# autoset-main.net
KiCad netlist of a schematic drawn in EAGLE
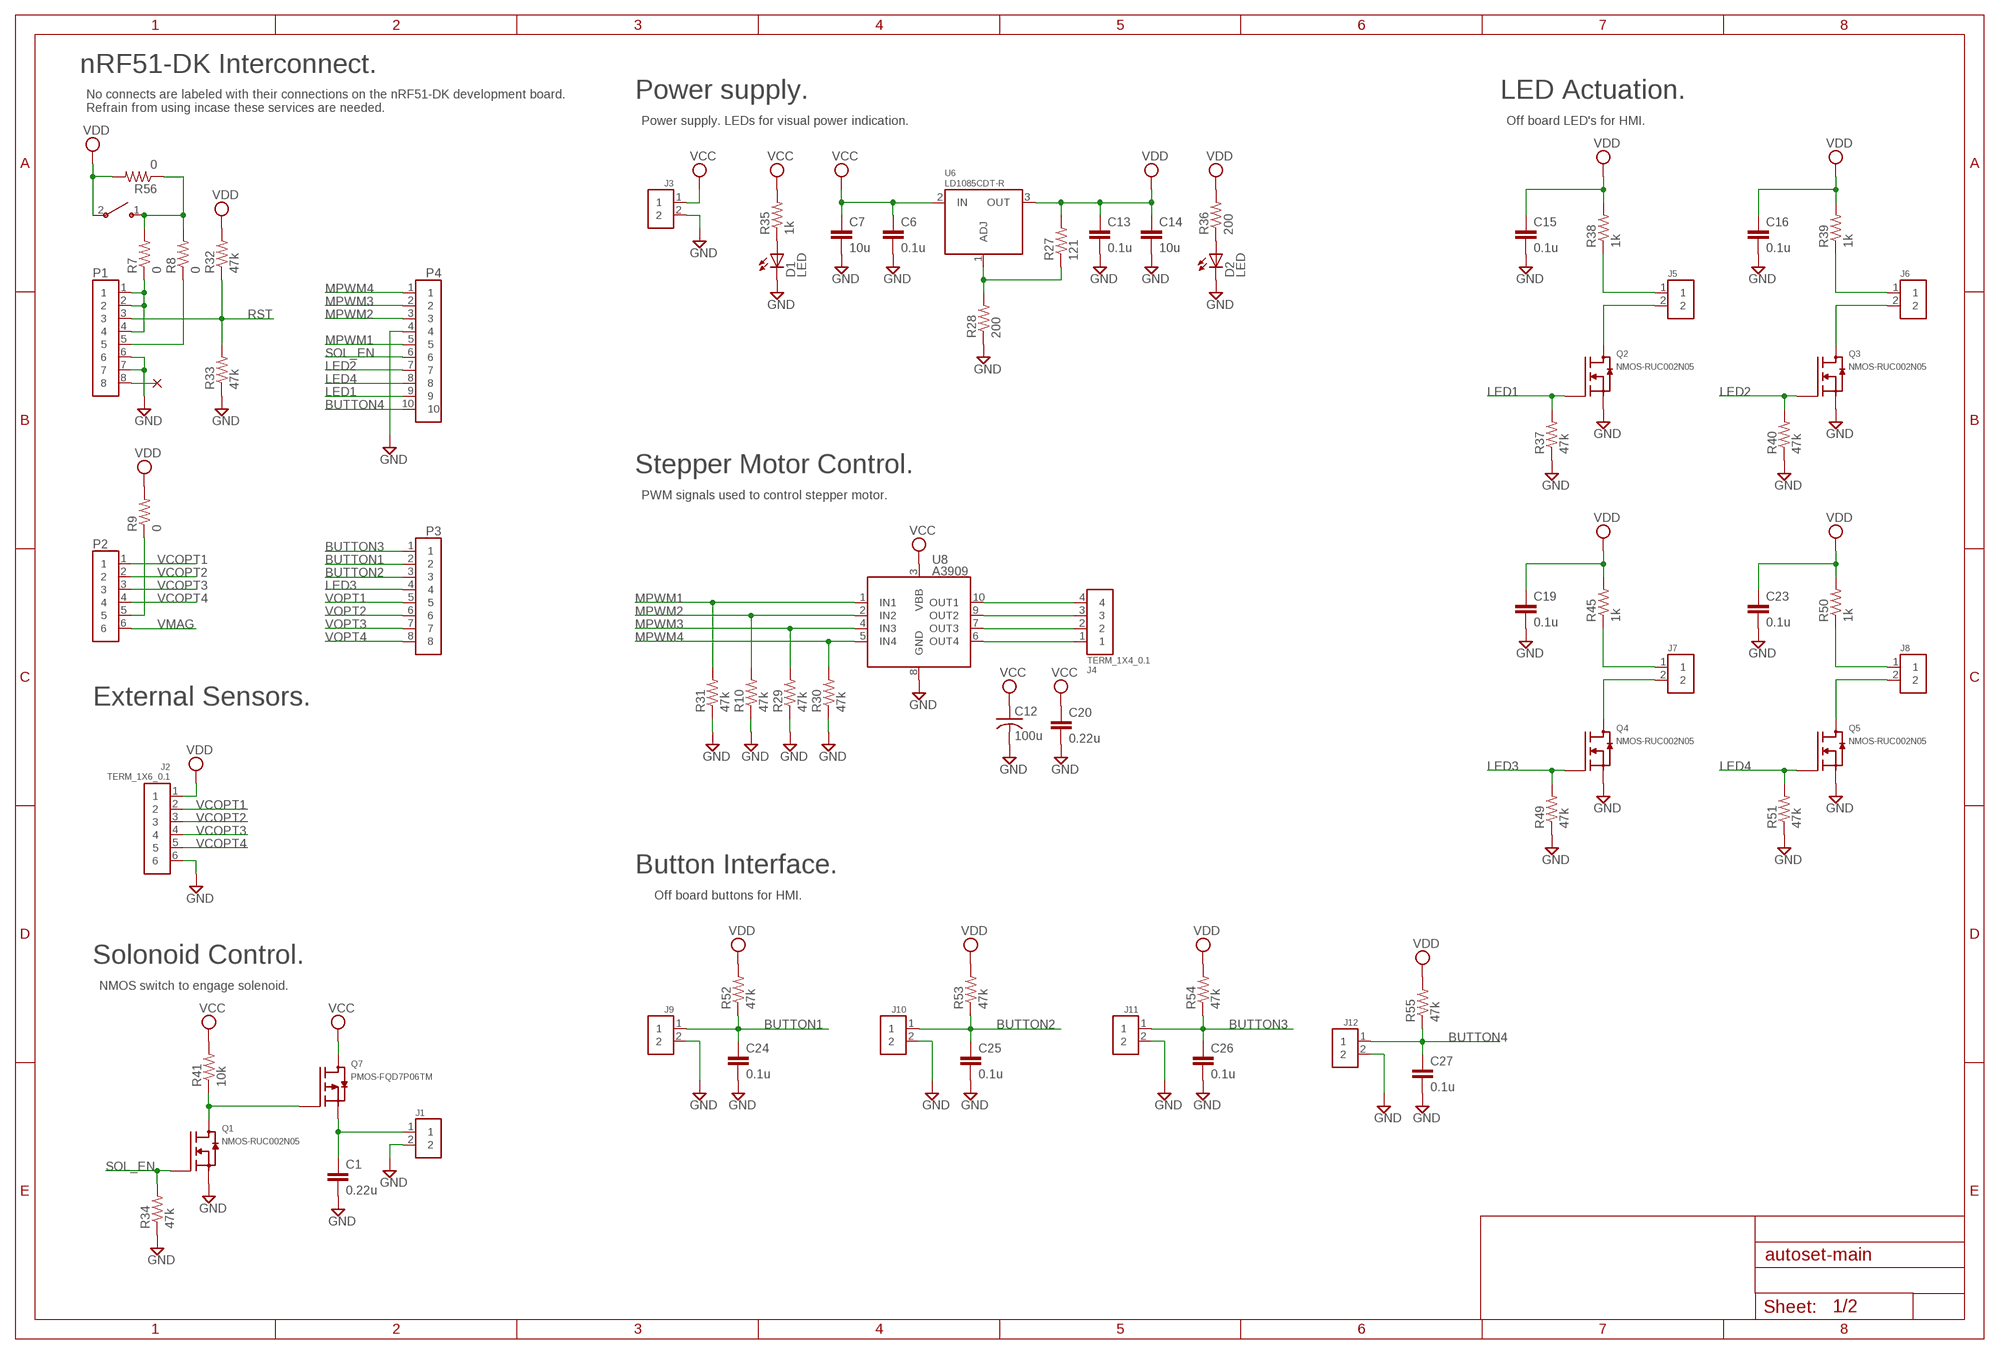
[diagram p0: schematic, sheet 1]
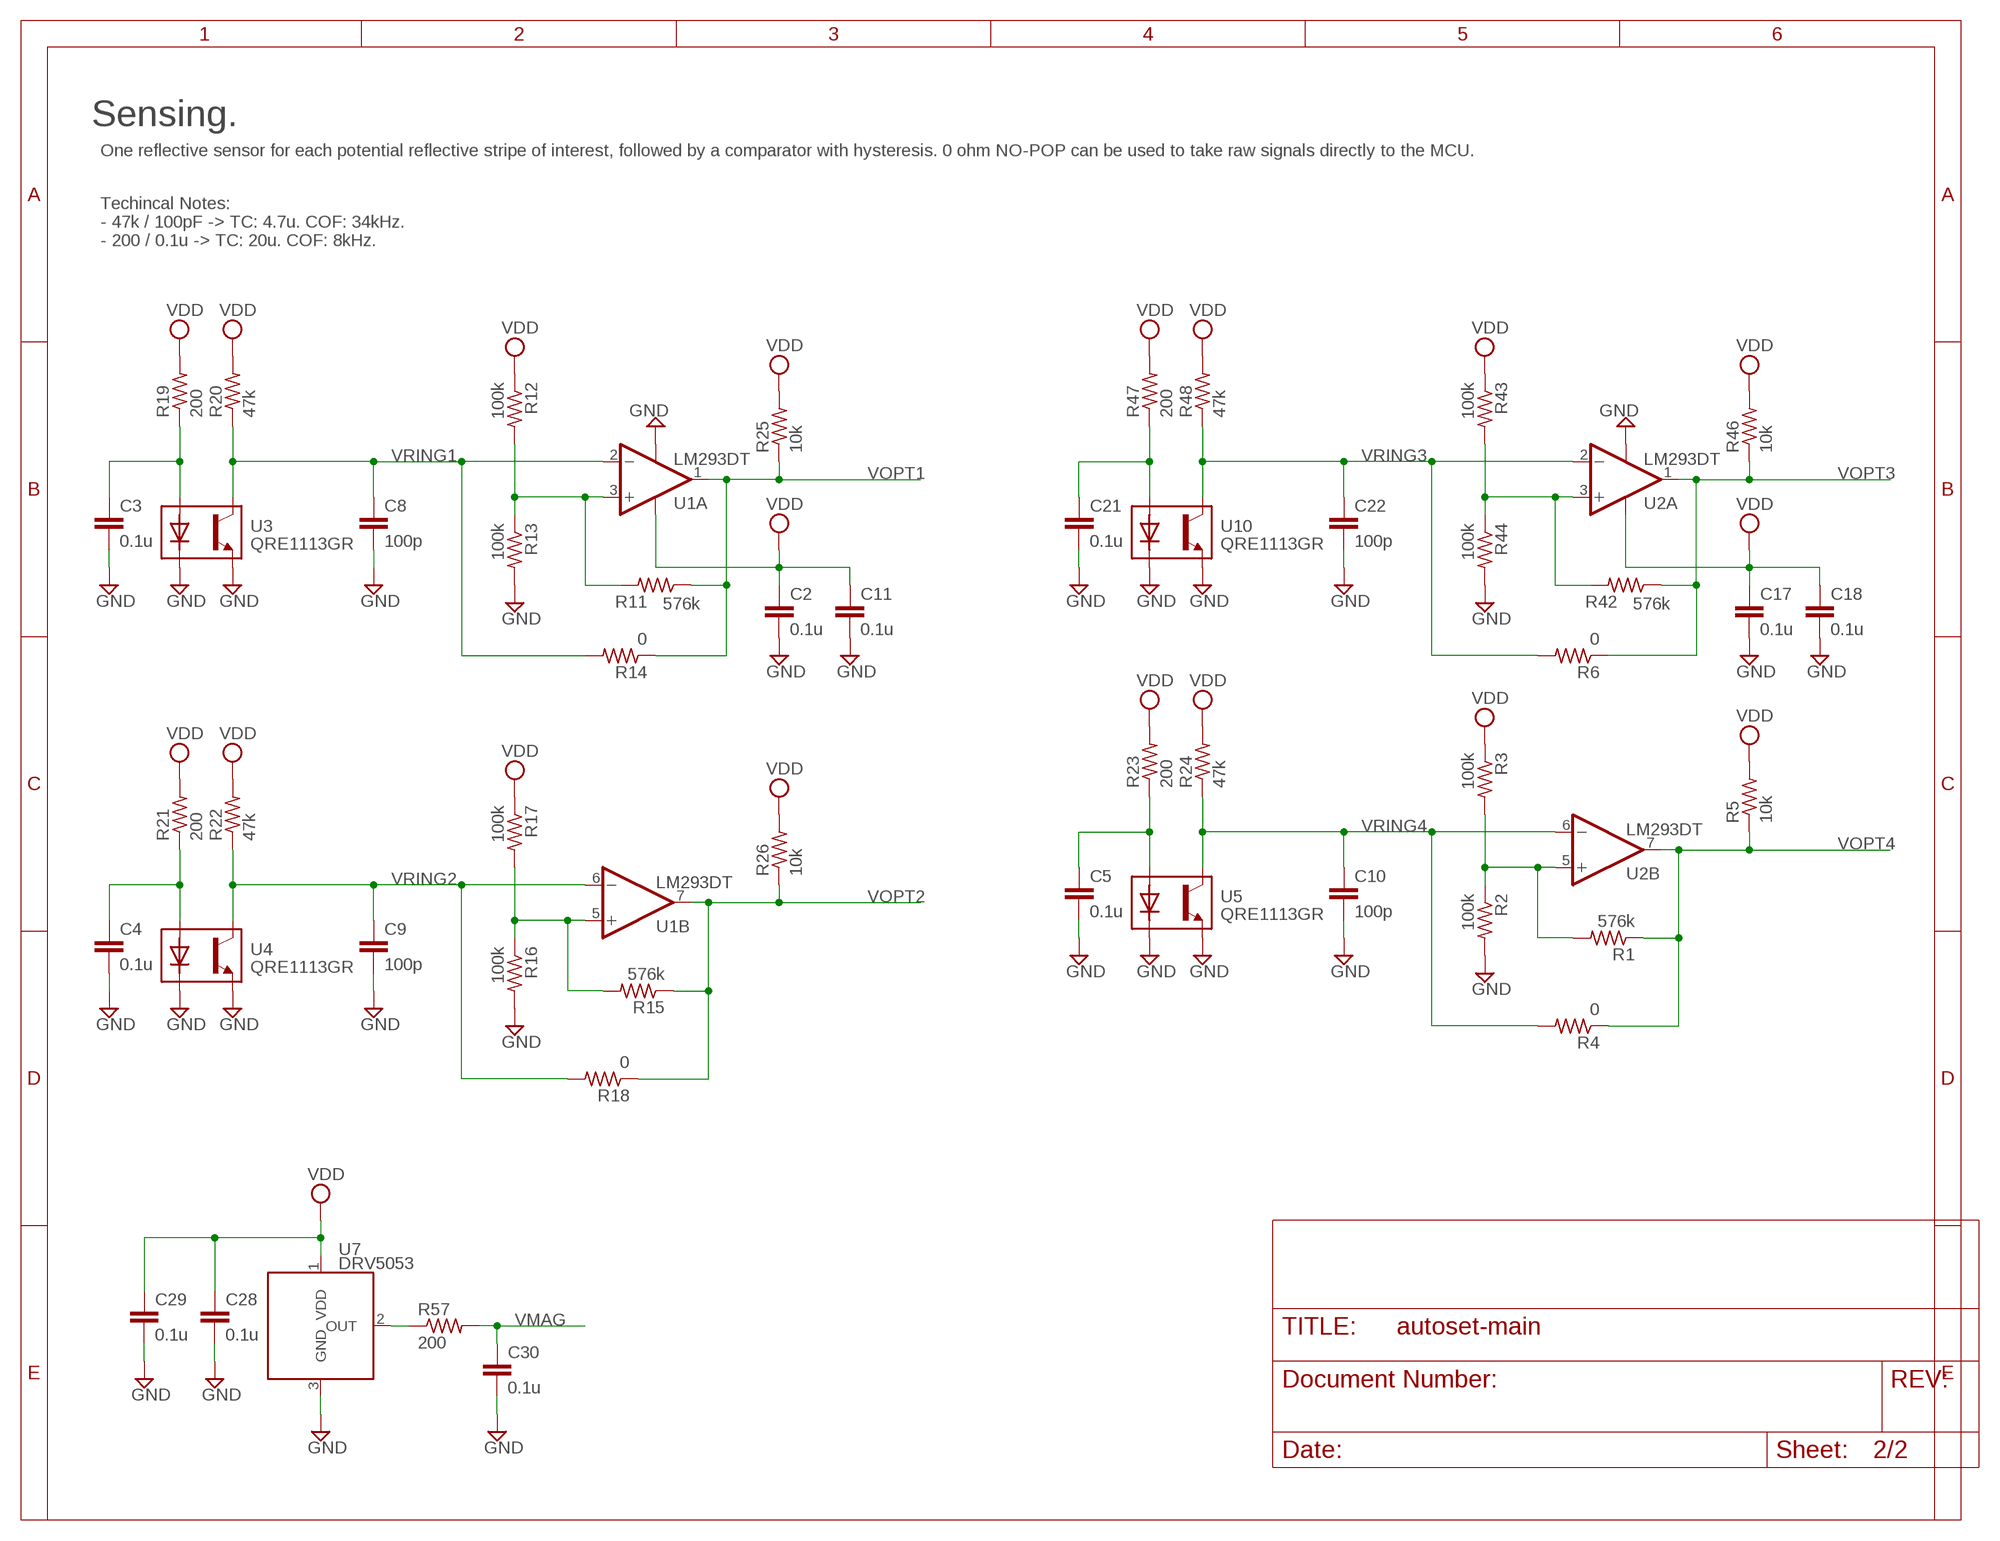
[diagram p1: schematic, sheet 2]

(export (version "E")
  (design (tool "Eeschema 10.0.6"))
  (components
    (comp (ref "C1")
      (value "0.22u")
      (footprint "eagle-import:C0603")
      (libsource (lib "eagle-import") (part "C0603"))
    )
    (comp (ref "C6")
      (value "0.1u")
      (footprint "eagle-import:C0603")
      (libsource (lib "eagle-import") (part "C0603"))
    )
    (comp (ref "C7")
      (value "10u")
      (footprint "eagle-import:C0603")
      (libsource (lib "eagle-import") (part "C0603"))
    )
    (comp (ref "C12")
      (value "100u")
      (footprint "eagle-import:CPOL-3.5MM")
      (libsource (lib "eagle-import") (part "C-POL3.5MM"))
    )
    (comp (ref "C13")
      (value "0.1u")
      (footprint "eagle-import:C0603")
      (libsource (lib "eagle-import") (part "C0603"))
    )
    (comp (ref "C14")
      (value "10u")
      (footprint "eagle-import:C0603")
      (libsource (lib "eagle-import") (part "C0603"))
    )
    (comp (ref "C15")
      (value "0.1u")
      (footprint "eagle-import:C0603")
      (libsource (lib "eagle-import") (part "C0603"))
    )
    (comp (ref "C16")
      (value "0.1u")
      (footprint "eagle-import:C0603")
      (libsource (lib "eagle-import") (part "C0603"))
    )
    (comp (ref "C19")
      (value "0.1u")
      (footprint "eagle-import:C0603")
      (libsource (lib "eagle-import") (part "C0603"))
    )
    (comp (ref "C20")
      (value "0.22u")
      (footprint "eagle-import:C0603")
      (libsource (lib "eagle-import") (part "C0603"))
    )
    (comp (ref "C23")
      (value "0.1u")
      (footprint "eagle-import:C0603")
      (libsource (lib "eagle-import") (part "C0603"))
    )
    (comp (ref "C24")
      (value "0.1u")
      (footprint "eagle-import:C0603")
      (libsource (lib "eagle-import") (part "C0603"))
    )
    (comp (ref "C25")
      (value "0.1u")
      (footprint "eagle-import:C0603")
      (libsource (lib "eagle-import") (part "C0603"))
    )
    (comp (ref "C26")
      (value "0.1u")
      (footprint "eagle-import:C0603")
      (libsource (lib "eagle-import") (part "C0603"))
    )
    (comp (ref "C27")
      (value "0.1u")
      (footprint "eagle-import:C0603")
      (libsource (lib "eagle-import") (part "C0603"))
    )
    (comp (ref "D1")
      (value "LED")
      (footprint "eagle-import:L0805")
      (libsource (lib "eagle-import") (part "LED"))
    )
    (comp (ref "D2")
      (value "LED")
      (footprint "eagle-import:L0805")
      (libsource (lib "eagle-import") (part "LED"))
    )
    (comp (ref "J1")
      (value "TERM_1X2_0.1")
      (footprint "eagle-import:TERM_1X2_0.1")
      (libsource (lib "eagle-import") (part "TERM_1X2_0.1"))
    )
    (comp (ref "J2")
      (value "TERM_1X6_0.1")
      (footprint "eagle-import:TERM_1X6_0.1")
      (libsource (lib "eagle-import") (part "TERM_1X6_0.1"))
    )
    (comp (ref "J3")
      (value "TERM_1X2_0.1")
      (footprint "eagle-import:TERM_1X2_0.1")
      (libsource (lib "eagle-import") (part "TERM_1X2_0.1"))
    )
    (comp (ref "J4")
      (value "TERM_1X4_0.1")
      (footprint "eagle-import:TERM_1X4_0.1")
      (libsource (lib "eagle-import") (part "TERM_1X4_0.1"))
    )
    (comp (ref "J5")
      (value "TERM_1X2_0.1")
      (footprint "eagle-import:TERM_1X2_0.1")
      (libsource (lib "eagle-import") (part "TERM_1X2_0.1"))
    )
    (comp (ref "J6")
      (value "TERM_1X2_0.1")
      (footprint "eagle-import:TERM_1X2_0.1")
      (libsource (lib "eagle-import") (part "TERM_1X2_0.1"))
    )
    (comp (ref "J7")
      (value "TERM_1X2_0.1")
      (footprint "eagle-import:TERM_1X2_0.1")
      (libsource (lib "eagle-import") (part "TERM_1X2_0.1"))
    )
    (comp (ref "J8")
      (value "TERM_1X2_0.1")
      (footprint "eagle-import:TERM_1X2_0.1")
      (libsource (lib "eagle-import") (part "TERM_1X2_0.1"))
    )
    (comp (ref "J9")
      (value "TERM_1X2_0.1")
      (footprint "eagle-import:TERM_1X2_0.1")
      (libsource (lib "eagle-import") (part "TERM_1X2_0.1"))
    )
    (comp (ref "J10")
      (value "TERM_1X2_0.1")
      (footprint "eagle-import:TERM_1X2_0.1")
      (libsource (lib "eagle-import") (part "TERM_1X2_0.1"))
    )
    (comp (ref "J11")
      (value "TERM_1X2_0.1")
      (footprint "eagle-import:TERM_1X2_0.1")
      (libsource (lib "eagle-import") (part "TERM_1X2_0.1"))
    )
    (comp (ref "J12")
      (value "TERM_1X2_0.1")
      (footprint "eagle-import:TERM_1X2_0.1")
      (libsource (lib "eagle-import") (part "TERM_1X2_0.1"))
    )
    (comp (ref "P1")
      (value "RECT_1X8")
      (footprint "eagle-import:RECT_1X8_0.1")
      (libsource (lib "eagle-import") (part "RECT_1X8"))
    )
    (comp (ref "P2")
      (value "RECT_1X6")
      (footprint "eagle-import:RECT_1X6_0.1")
      (libsource (lib "eagle-import") (part "RECT_1X6"))
    )
    (comp (ref "P3")
      (value "RECT_1X8")
      (footprint "eagle-import:RECT_1X8_0.1")
      (libsource (lib "eagle-import") (part "RECT_1X8"))
    )
    (comp (ref "P4")
      (value "RECT_1X10")
      (footprint "eagle-import:RECT_1X10_0.1")
      (libsource (lib "eagle-import") (part "RECT_1X10"))
    )
    (comp (ref "Q1")
      (value "NMOS-RUC002N05")
      (footprint "eagle-import:SOT23")
      (libsource (lib "eagle-import") (part "NMOS-RUC002N05"))
    )
    (comp (ref "Q2")
      (value "NMOS-RUC002N05")
      (footprint "eagle-import:SOT23")
      (libsource (lib "eagle-import") (part "NMOS-RUC002N05"))
    )
    (comp (ref "Q3")
      (value "NMOS-RUC002N05")
      (footprint "eagle-import:SOT23")
      (libsource (lib "eagle-import") (part "NMOS-RUC002N05"))
    )
    (comp (ref "Q4")
      (value "NMOS-RUC002N05")
      (footprint "eagle-import:SOT23")
      (libsource (lib "eagle-import") (part "NMOS-RUC002N05"))
    )
    (comp (ref "Q5")
      (value "NMOS-RUC002N05")
      (footprint "eagle-import:SOT23")
      (libsource (lib "eagle-import") (part "NMOS-RUC002N05"))
    )
    (comp (ref "Q7")
      (value "PMOS-FQD7P06TM")
      (footprint "eagle-import:TO252")
      (libsource (lib "eagle-import") (part "PMOS-FQD7P06TM"))
    )
    (comp (ref "R7")
      (value "0")
      (footprint "eagle-import:R0603")
      (libsource (lib "eagle-import") (part "R0603"))
    )
    (comp (ref "R8")
      (value "0")
      (footprint "eagle-import:R0603")
      (libsource (lib "eagle-import") (part "R0603"))
    )
    (comp (ref "R9")
      (value "0")
      (footprint "eagle-import:R0603")
      (libsource (lib "eagle-import") (part "R0603"))
    )
    (comp (ref "R10")
      (value "47k")
      (footprint "eagle-import:R0603")
      (libsource (lib "eagle-import") (part "R0603"))
    )
    (comp (ref "R27")
      (value "121")
      (footprint "eagle-import:R0603")
      (libsource (lib "eagle-import") (part "R0603"))
    )
    (comp (ref "R28")
      (value "200")
      (footprint "eagle-import:R0603")
      (libsource (lib "eagle-import") (part "R0603"))
    )
    (comp (ref "R29")
      (value "47k")
      (footprint "eagle-import:R0603")
      (libsource (lib "eagle-import") (part "R0603"))
    )
    (comp (ref "R30")
      (value "47k")
      (footprint "eagle-import:R0603")
      (libsource (lib "eagle-import") (part "R0603"))
    )
    (comp (ref "R31")
      (value "47k")
      (footprint "eagle-import:R0603")
      (libsource (lib "eagle-import") (part "R0603"))
    )
    (comp (ref "R32")
      (value "47k")
      (footprint "eagle-import:R0603")
      (libsource (lib "eagle-import") (part "R0603"))
    )
    (comp (ref "R33")
      (value "47k")
      (footprint "eagle-import:R0603")
      (libsource (lib "eagle-import") (part "R0603"))
    )
    (comp (ref "R34")
      (value "47k")
      (footprint "eagle-import:R0603")
      (libsource (lib "eagle-import") (part "R0603"))
    )
    (comp (ref "R35")
      (value "1k")
      (footprint "eagle-import:R0603")
      (libsource (lib "eagle-import") (part "R0603"))
    )
    (comp (ref "R36")
      (value "200")
      (footprint "eagle-import:R0603")
      (libsource (lib "eagle-import") (part "R0603"))
    )
    (comp (ref "R37")
      (value "47k")
      (footprint "eagle-import:R0603")
      (libsource (lib "eagle-import") (part "R0603"))
    )
    (comp (ref "R38")
      (value "1k")
      (footprint "eagle-import:R0603")
      (libsource (lib "eagle-import") (part "R0603"))
    )
    (comp (ref "R39")
      (value "1k")
      (footprint "eagle-import:R0603")
      (libsource (lib "eagle-import") (part "R0603"))
    )
    (comp (ref "R40")
      (value "47k")
      (footprint "eagle-import:R0603")
      (libsource (lib "eagle-import") (part "R0603"))
    )
    (comp (ref "R41")
      (value "10k")
      (footprint "eagle-import:R0603")
      (libsource (lib "eagle-import") (part "R0603"))
    )
    (comp (ref "R45")
      (value "1k")
      (footprint "eagle-import:R0603")
      (libsource (lib "eagle-import") (part "R0603"))
    )
    (comp (ref "R49")
      (value "47k")
      (footprint "eagle-import:R0603")
      (libsource (lib "eagle-import") (part "R0603"))
    )
    (comp (ref "R50")
      (value "1k")
      (footprint "eagle-import:R0603")
      (libsource (lib "eagle-import") (part "R0603"))
    )
    (comp (ref "R51")
      (value "47k")
      (footprint "eagle-import:R0603")
      (libsource (lib "eagle-import") (part "R0603"))
    )
    (comp (ref "R52")
      (value "47k")
      (footprint "eagle-import:R0603")
      (libsource (lib "eagle-import") (part "R0603"))
    )
    (comp (ref "R53")
      (value "47k")
      (footprint "eagle-import:R0603")
      (libsource (lib "eagle-import") (part "R0603"))
    )
    (comp (ref "R54")
      (value "47k")
      (footprint "eagle-import:R0603")
      (libsource (lib "eagle-import") (part "R0603"))
    )
    (comp (ref "R55")
      (value "47k")
      (footprint "eagle-import:R0603")
      (libsource (lib "eagle-import") (part "R0603"))
    )
    (comp (ref "R56")
      (value "0")
      (footprint "eagle-import:R0603")
      (libsource (lib "eagle-import") (part "R0603"))
    )
    (comp (ref "SW1")
      (value "GPTS203211B")
      (footprint "eagle-import:GPTS203211B")
      (libsource (lib "eagle-import") (part "GPTS203211B"))
    )
    (comp (ref "U6")
      (value "LD1085CDT-R")
      (footprint "eagle-import:TO252")
      (libsource (lib "eagle-import") (part "LD1085CDT-R"))
    )
    (comp (ref "U8")
      (value "A3909")
      (footprint "eagle-import:SSOP10")
      (libsource (lib "eagle-import") (part "A3909"))
    )
    (comp (ref "Z15")
      (value "NC")
      (footprint "eagle-import:NC_TH")
      (libsource (lib "eagle-import") (part "NC"))
    )
    (comp (ref "C2")
      (value "0.1u")
      (footprint "eagle-import:C0603")
      (libsource (lib "eagle-import") (part "C0603"))
    )
    (comp (ref "C3")
      (value "0.1u")
      (footprint "eagle-import:C0603")
      (libsource (lib "eagle-import") (part "C0603"))
    )
    (comp (ref "C4")
      (value "0.1u")
      (footprint "eagle-import:C0603")
      (libsource (lib "eagle-import") (part "C0603"))
    )
    (comp (ref "C5")
      (value "0.1u")
      (footprint "eagle-import:C0603")
      (libsource (lib "eagle-import") (part "C0603"))
    )
    (comp (ref "C8")
      (value "100p")
      (footprint "eagle-import:C0603")
      (libsource (lib "eagle-import") (part "C0603"))
    )
    (comp (ref "C9")
      (value "100p")
      (footprint "eagle-import:C0603")
      (libsource (lib "eagle-import") (part "C0603"))
    )
    (comp (ref "C10")
      (value "100p")
      (footprint "eagle-import:C0603")
      (libsource (lib "eagle-import") (part "C0603"))
    )
    (comp (ref "C11")
      (value "0.1u")
      (footprint "eagle-import:C0603")
      (libsource (lib "eagle-import") (part "C0603"))
    )
    (comp (ref "C17")
      (value "0.1u")
      (footprint "eagle-import:C0603")
      (libsource (lib "eagle-import") (part "C0603"))
    )
    (comp (ref "C18")
      (value "0.1u")
      (footprint "eagle-import:C0603")
      (libsource (lib "eagle-import") (part "C0603"))
    )
    (comp (ref "C21")
      (value "0.1u")
      (footprint "eagle-import:C0603")
      (libsource (lib "eagle-import") (part "C0603"))
    )
    (comp (ref "C22")
      (value "100p")
      (footprint "eagle-import:C0603")
      (libsource (lib "eagle-import") (part "C0603"))
    )
    (comp (ref "C28")
      (value "0.1u")
      (footprint "eagle-import:C0603")
      (libsource (lib "eagle-import") (part "C0603"))
    )
    (comp (ref "C29")
      (value "0.1u")
      (footprint "eagle-import:C0603")
      (libsource (lib "eagle-import") (part "C0603"))
    )
    (comp (ref "C30")
      (value "0.1u")
      (footprint "eagle-import:C0603")
      (libsource (lib "eagle-import") (part "C0603"))
    )
    (comp (ref "R1")
      (value "576k")
      (footprint "eagle-import:R0603")
      (libsource (lib "eagle-import") (part "R0603"))
    )
    (comp (ref "R2")
      (value "100k")
      (footprint "eagle-import:R0603")
      (libsource (lib "eagle-import") (part "R0603"))
    )
    (comp (ref "R3")
      (value "100k")
      (footprint "eagle-import:R0603")
      (libsource (lib "eagle-import") (part "R0603"))
    )
    (comp (ref "R4")
      (value "0")
      (footprint "eagle-import:R0603")
      (libsource (lib "eagle-import") (part "R0603"))
    )
    (comp (ref "R5")
      (value "10k")
      (footprint "eagle-import:R0603")
      (libsource (lib "eagle-import") (part "R0603"))
    )
    (comp (ref "R6")
      (value "0")
      (footprint "eagle-import:R0603")
      (libsource (lib "eagle-import") (part "R0603"))
    )
    (comp (ref "R11")
      (value "576k")
      (footprint "eagle-import:R0603")
      (libsource (lib "eagle-import") (part "R0603"))
    )
    (comp (ref "R12")
      (value "100k")
      (footprint "eagle-import:R0603")
      (libsource (lib "eagle-import") (part "R0603"))
    )
    (comp (ref "R13")
      (value "100k")
      (footprint "eagle-import:R0603")
      (libsource (lib "eagle-import") (part "R0603"))
    )
    (comp (ref "R14")
      (value "0")
      (footprint "eagle-import:R0603")
      (libsource (lib "eagle-import") (part "R0603"))
    )
    (comp (ref "R15")
      (value "576k")
      (footprint "eagle-import:R0603")
      (libsource (lib "eagle-import") (part "R0603"))
    )
    (comp (ref "R16")
      (value "100k")
      (footprint "eagle-import:R0603")
      (libsource (lib "eagle-import") (part "R0603"))
    )
    (comp (ref "R17")
      (value "100k")
      (footprint "eagle-import:R0603")
      (libsource (lib "eagle-import") (part "R0603"))
    )
    (comp (ref "R18")
      (value "0")
      (footprint "eagle-import:R0603")
      (libsource (lib "eagle-import") (part "R0603"))
    )
    (comp (ref "R19")
      (value "200")
      (footprint "eagle-import:R0603")
      (libsource (lib "eagle-import") (part "R0603"))
    )
    (comp (ref "R20")
      (value "47k")
      (footprint "eagle-import:R0603")
      (libsource (lib "eagle-import") (part "R0603"))
    )
    (comp (ref "R21")
      (value "200")
      (footprint "eagle-import:R0603")
      (libsource (lib "eagle-import") (part "R0603"))
    )
    (comp (ref "R22")
      (value "47k")
      (footprint "eagle-import:R0603")
      (libsource (lib "eagle-import") (part "R0603"))
    )
    (comp (ref "R23")
      (value "200")
      (footprint "eagle-import:R0603")
      (libsource (lib "eagle-import") (part "R0603"))
    )
    (comp (ref "R24")
      (value "47k")
      (footprint "eagle-import:R0603")
      (libsource (lib "eagle-import") (part "R0603"))
    )
    (comp (ref "R25")
      (value "10k")
      (footprint "eagle-import:R0603")
      (libsource (lib "eagle-import") (part "R0603"))
    )
    (comp (ref "R26")
      (value "10k")
      (footprint "eagle-import:R0603")
      (libsource (lib "eagle-import") (part "R0603"))
    )
    (comp (ref "R42")
      (value "576k")
      (footprint "eagle-import:R0603")
      (libsource (lib "eagle-import") (part "R0603"))
    )
    (comp (ref "R43")
      (value "100k")
      (footprint "eagle-import:R0603")
      (libsource (lib "eagle-import") (part "R0603"))
    )
    (comp (ref "R44")
      (value "100k")
      (footprint "eagle-import:R0603")
      (libsource (lib "eagle-import") (part "R0603"))
    )
    (comp (ref "R46")
      (value "10k")
      (footprint "eagle-import:R0603")
      (libsource (lib "eagle-import") (part "R0603"))
    )
    (comp (ref "R47")
      (value "200")
      (footprint "eagle-import:R0603")
      (libsource (lib "eagle-import") (part "R0603"))
    )
    (comp (ref "R48")
      (value "47k")
      (footprint "eagle-import:R0603")
      (libsource (lib "eagle-import") (part "R0603"))
    )
    (comp (ref "R57")
      (value "200")
      (footprint "eagle-import:R0603")
      (libsource (lib "eagle-import") (part "R0603"))
    )
    (comp (ref "U1")
      (value "LM293DT")
      (footprint "eagle-import:SOIC8")
      (fields (field (name "DKPN") "497-1566-1-ND"))
      (libsource (lib "eagle-import") (part "LM293DT"))
    )
    (comp (ref "U2")
      (value "LM293DT")
      (footprint "eagle-import:SOIC8")
      (fields (field (name "DKPN") "497-1566-1-ND"))
      (libsource (lib "eagle-import") (part "LM293DT"))
    )
    (comp (ref "U3")
      (value "QRE1113GR")
      (footprint "eagle-import:REFL")
      (libsource (lib "eagle-import") (part "QRE1113GR"))
    )
    (comp (ref "U4")
      (value "QRE1113GR")
      (footprint "eagle-import:REFL")
      (libsource (lib "eagle-import") (part "QRE1113GR"))
    )
    (comp (ref "U5")
      (value "QRE1113GR")
      (footprint "eagle-import:REFL")
      (libsource (lib "eagle-import") (part "QRE1113GR"))
    )
    (comp (ref "U7")
      (value "DRV5053")
      (footprint "eagle-import:SOT23")
      (libsource (lib "eagle-import") (part "DRV5053"))
    )
    (comp (ref "U10")
      (value "QRE1113GR")
      (footprint "eagle-import:REFL")
      (libsource (lib "eagle-import") (part "QRE1113GR"))
    )
  )
  (nets
    (net (code "1") (name "BUTTON1") (class "Default")
      (node (ref "C24") (pin "1") (pinfunction "1_1") (pintype "passive"))
      (node (ref "J9") (pin "1") (pinfunction "1_1") (pintype "bidirectional"))
      (node (ref "P3") (pin "2") (pinfunction "2_2") (pintype "bidirectional"))
      (node (ref "R52") (pin "1") (pinfunction "1_1") (pintype "passive"))
    )
    (net (code "2") (name "BUTTON2") (class "Default")
      (node (ref "C25") (pin "1") (pinfunction "1_1") (pintype "passive"))
      (node (ref "J10") (pin "1") (pinfunction "1_1") (pintype "bidirectional"))
      (node (ref "P3") (pin "3") (pinfunction "3_3") (pintype "bidirectional"))
      (node (ref "R53") (pin "1") (pinfunction "1_1") (pintype "passive"))
    )
    (net (code "3") (name "BUTTON3") (class "Default")
      (node (ref "C26") (pin "1") (pinfunction "1_1") (pintype "passive"))
      (node (ref "J11") (pin "1") (pinfunction "1_1") (pintype "bidirectional"))
      (node (ref "P3") (pin "1") (pinfunction "1_1") (pintype "bidirectional"))
      (node (ref "R54") (pin "1") (pinfunction "1_1") (pintype "passive"))
    )
    (net (code "4") (name "BUTTON4") (class "Default")
      (node (ref "C27") (pin "1") (pinfunction "1_1") (pintype "passive"))
      (node (ref "J12") (pin "1") (pinfunction "1_1") (pintype "bidirectional"))
      (node (ref "P4") (pin "10") (pinfunction "10_10") (pintype "bidirectional"))
      (node (ref "R55") (pin "1") (pinfunction "1_1") (pintype "passive"))
    )
    (net (code "5") (name "GND") (class "Default")
      (node (ref "C1") (pin "2") (pinfunction "2_2") (pintype "passive"))
      (node (ref "C10") (pin "2") (pinfunction "2_2") (pintype "passive"))
      (node (ref "C11") (pin "2") (pinfunction "2_2") (pintype "passive"))
      (node (ref "C12") (pin "P$2") (pinfunction "2_P$2") (pintype "passive"))
      (node (ref "C13") (pin "2") (pinfunction "2_2") (pintype "passive"))
      (node (ref "C14") (pin "2") (pinfunction "2_2") (pintype "passive"))
      (node (ref "C15") (pin "2") (pinfunction "2_2") (pintype "passive"))
      (node (ref "C16") (pin "2") (pinfunction "2_2") (pintype "passive"))
      (node (ref "C17") (pin "2") (pinfunction "2_2") (pintype "passive"))
      (node (ref "C18") (pin "2") (pinfunction "2_2") (pintype "passive"))
      (node (ref "C19") (pin "2") (pinfunction "2_2") (pintype "passive"))
      (node (ref "C2") (pin "2") (pinfunction "2_2") (pintype "passive"))
      (node (ref "C20") (pin "2") (pinfunction "2_2") (pintype "passive"))
      (node (ref "C21") (pin "2") (pinfunction "2_2") (pintype "passive"))
      (node (ref "C22") (pin "2") (pinfunction "2_2") (pintype "passive"))
      (node (ref "C23") (pin "2") (pinfunction "2_2") (pintype "passive"))
      (node (ref "C24") (pin "2") (pinfunction "2_2") (pintype "passive"))
      (node (ref "C25") (pin "2") (pinfunction "2_2") (pintype "passive"))
      (node (ref "C26") (pin "2") (pinfunction "2_2") (pintype "passive"))
      (node (ref "C27") (pin "2") (pinfunction "2_2") (pintype "passive"))
      (node (ref "C28") (pin "2") (pinfunction "2_2") (pintype "passive"))
      (node (ref "C29") (pin "2") (pinfunction "2_2") (pintype "passive"))
      (node (ref "C3") (pin "2") (pinfunction "2_2") (pintype "passive"))
      (node (ref "C30") (pin "2") (pinfunction "2_2") (pintype "passive"))
      (node (ref "C4") (pin "2") (pinfunction "2_2") (pintype "passive"))
      (node (ref "C5") (pin "2") (pinfunction "2_2") (pintype "passive"))
      (node (ref "C6") (pin "2") (pinfunction "2_2") (pintype "passive"))
      (node (ref "C7") (pin "2") (pinfunction "2_2") (pintype "passive"))
      (node (ref "C8") (pin "2") (pinfunction "2_2") (pintype "passive"))
      (node (ref "C9") (pin "2") (pinfunction "2_2") (pintype "passive"))
      (node (ref "D1") (pin "2") (pinfunction "C_2") (pintype "passive"))
      (node (ref "D2") (pin "2") (pinfunction "C_2") (pintype "passive"))
      (node (ref "J1") (pin "2") (pinfunction "2_2") (pintype "bidirectional"))
      (node (ref "J10") (pin "2") (pinfunction "2_2") (pintype "bidirectional"))
      (node (ref "J11") (pin "2") (pinfunction "2_2") (pintype "bidirectional"))
      (node (ref "J12") (pin "2") (pinfunction "2_2") (pintype "bidirectional"))
      (node (ref "J2") (pin "6") (pinfunction "6_6") (pintype "bidirectional"))
      (node (ref "J3") (pin "2") (pinfunction "2_2") (pintype "bidirectional"))
      (node (ref "J9") (pin "2") (pinfunction "2_2") (pintype "bidirectional"))
      (node (ref "P1") (pin "6") (pinfunction "6_6") (pintype "bidirectional"))
      (node (ref "P1") (pin "7") (pinfunction "7_7") (pintype "bidirectional"))
      (node (ref "P4") (pin "4") (pinfunction "4_4") (pintype "bidirectional"))
      (node (ref "Q1") (pin "1") (pinfunction "S_1") (pintype "bidirectional"))
      (node (ref "Q2") (pin "1") (pinfunction "S_1") (pintype "bidirectional"))
      (node (ref "Q3") (pin "1") (pinfunction "S_1") (pintype "bidirectional"))
      (node (ref "Q4") (pin "1") (pinfunction "S_1") (pintype "bidirectional"))
      (node (ref "Q5") (pin "1") (pinfunction "S_1") (pintype "bidirectional"))
      (node (ref "R10") (pin "1") (pinfunction "1_1") (pintype "passive"))
      (node (ref "R13") (pin "2") (pinfunction "2_2") (pintype "passive"))
      (node (ref "R16") (pin "2") (pinfunction "2_2") (pintype "passive"))
      (node (ref "R2") (pin "2") (pinfunction "2_2") (pintype "passive"))
      (node (ref "R28") (pin "1") (pinfunction "1_1") (pintype "passive"))
      (node (ref "R29") (pin "1") (pinfunction "1_1") (pintype "passive"))
      (node (ref "R30") (pin "1") (pinfunction "1_1") (pintype "passive"))
      (node (ref "R31") (pin "1") (pinfunction "1_1") (pintype "passive"))
      (node (ref "R33") (pin "1") (pinfunction "1_1") (pintype "passive"))
      (node (ref "R34") (pin "1") (pinfunction "1_1") (pintype "passive"))
      (node (ref "R37") (pin "1") (pinfunction "1_1") (pintype "passive"))
      (node (ref "R40") (pin "1") (pinfunction "1_1") (pintype "passive"))
      (node (ref "R44") (pin "2") (pinfunction "2_2") (pintype "passive"))
      (node (ref "R49") (pin "1") (pinfunction "1_1") (pintype "passive"))
      (node (ref "R51") (pin "1") (pinfunction "1_1") (pintype "passive"))
      (node (ref "U1") (pin "4") (pinfunction "V-_4") (pintype "power_in"))
      (node (ref "U10") (pin "2") (pinfunction "DC_2") (pintype "passive"))
      (node (ref "U10") (pin "4") (pinfunction "E_4") (pintype "passive"))
      (node (ref "U2") (pin "4") (pinfunction "V-_4") (pintype "power_in"))
      (node (ref "U3") (pin "2") (pinfunction "DC_2") (pintype "passive"))
      (node (ref "U3") (pin "4") (pinfunction "E_4") (pintype "passive"))
      (node (ref "U4") (pin "2") (pinfunction "DC_2") (pintype "passive"))
      (node (ref "U4") (pin "4") (pinfunction "E_4") (pintype "passive"))
      (node (ref "U5") (pin "2") (pinfunction "DC_2") (pintype "passive"))
      (node (ref "U5") (pin "4") (pinfunction "E_4") (pintype "passive"))
      (node (ref "U7") (pin "3") (pinfunction "GND_3") (pintype "bidirectional"))
      (node (ref "U8") (pin "8") (pinfunction "GND_8") (pintype "bidirectional"))
    )
    (net (code "6") (name "LED1") (class "Default")
      (node (ref "P4") (pin "9") (pinfunction "9_9") (pintype "bidirectional"))
      (node (ref "Q2") (pin "2") (pinfunction "G_2") (pintype "bidirectional"))
      (node (ref "R37") (pin "2") (pinfunction "2_2") (pintype "passive"))
    )
    (net (code "7") (name "LED2") (class "Default")
      (node (ref "P4") (pin "7") (pinfunction "7_7") (pintype "bidirectional"))
      (node (ref "Q3") (pin "2") (pinfunction "G_2") (pintype "bidirectional"))
      (node (ref "R40") (pin "2") (pinfunction "2_2") (pintype "passive"))
    )
    (net (code "8") (name "LED3") (class "Default")
      (node (ref "P3") (pin "4") (pinfunction "4_4") (pintype "bidirectional"))
      (node (ref "Q4") (pin "2") (pinfunction "G_2") (pintype "bidirectional"))
      (node (ref "R49") (pin "2") (pinfunction "2_2") (pintype "passive"))
    )
    (net (code "9") (name "LED4") (class "Default")
      (node (ref "P4") (pin "8") (pinfunction "8_8") (pintype "bidirectional"))
      (node (ref "Q5") (pin "2") (pinfunction "G_2") (pintype "bidirectional"))
      (node (ref "R51") (pin "2") (pinfunction "2_2") (pintype "passive"))
    )
    (net (code "10") (name "MPWM1") (class "Default")
      (node (ref "P4") (pin "5") (pinfunction "5_5") (pintype "bidirectional"))
      (node (ref "R31") (pin "2") (pinfunction "2_2") (pintype "passive"))
      (node (ref "U8") (pin "1") (pinfunction "IN1_1") (pintype "bidirectional"))
    )
    (net (code "11") (name "MPWM2") (class "Default")
      (node (ref "P4") (pin "3") (pinfunction "3_3") (pintype "bidirectional"))
      (node (ref "R10") (pin "2") (pinfunction "2_2") (pintype "passive"))
      (node (ref "U8") (pin "2") (pinfunction "IN2_2") (pintype "bidirectional"))
    )
    (net (code "12") (name "MPWM3") (class "Default")
      (node (ref "P4") (pin "2") (pinfunction "2_2") (pintype "bidirectional"))
      (node (ref "R29") (pin "2") (pinfunction "2_2") (pintype "passive"))
      (node (ref "U8") (pin "4") (pinfunction "IN3_4") (pintype "bidirectional"))
    )
    (net (code "13") (name "MPWM4") (class "Default")
      (node (ref "P4") (pin "1") (pinfunction "1_1") (pintype "bidirectional"))
      (node (ref "R30") (pin "2") (pinfunction "2_2") (pintype "passive"))
      (node (ref "U8") (pin "5") (pinfunction "IN4_5") (pintype "bidirectional"))
    )
    (net (code "14") (name "Net-(D1-A)") (class "Default")
      (node (ref "D1") (pin "1") (pinfunction "A_1") (pintype "passive"))
      (node (ref "R35") (pin "1") (pinfunction "1_1") (pintype "passive"))
    )
    (net (code "15") (name "Net-(D2-A)") (class "Default")
      (node (ref "D2") (pin "1") (pinfunction "A_1") (pintype "passive"))
      (node (ref "R36") (pin "1") (pinfunction "1_1") (pintype "passive"))
    )
    (net (code "16") (name "Net-(J5-Pad1)") (class "Default")
      (node (ref "J5") (pin "1") (pinfunction "1_1") (pintype "bidirectional"))
      (node (ref "R38") (pin "1") (pinfunction "1_1") (pintype "passive"))
    )
    (net (code "17") (name "Net-(J6-Pad1)") (class "Default")
      (node (ref "J6") (pin "1") (pinfunction "1_1") (pintype "bidirectional"))
      (node (ref "R39") (pin "1") (pinfunction "1_1") (pintype "passive"))
    )
    (net (code "18") (name "Net-(J7-Pad1)") (class "Default")
      (node (ref "J7") (pin "1") (pinfunction "1_1") (pintype "bidirectional"))
      (node (ref "R45") (pin "1") (pinfunction "1_1") (pintype "passive"))
    )
    (net (code "19") (name "Net-(J8-Pad1)") (class "Default")
      (node (ref "J8") (pin "1") (pinfunction "1_1") (pintype "bidirectional"))
      (node (ref "R50") (pin "1") (pinfunction "1_1") (pintype "passive"))
    )
    (net (code "20") (name "Net-(P1-Pad1)") (class "Default")
      (node (ref "P1") (pin "1") (pinfunction "1_1") (pintype "bidirectional"))
      (node (ref "P1") (pin "2") (pinfunction "2_2") (pintype "bidirectional"))
      (node (ref "P1") (pin "4") (pinfunction "4_4") (pintype "bidirectional"))
      (node (ref "R7") (pin "1") (pinfunction "1_1") (pintype "passive"))
    )
    (net (code "21") (name "Net-(P1-Pad5)") (class "Default")
      (node (ref "P1") (pin "5") (pinfunction "5_5") (pintype "bidirectional"))
      (node (ref "R8") (pin "1") (pinfunction "1_1") (pintype "passive"))
    )
    (net (code "22") (name "Net-(P1-Pad8)") (class "Default")
      (node (ref "P1") (pin "8") (pinfunction "8_8") (pintype "bidirectional"))
      (node (ref "Z15") (pin "P$1") (pinfunction "P$1_P$1") (pintype "bidirectional"))
    )
    (net (code "23") (name "Net-(P2-Pad5)") (class "Default")
      (node (ref "P2") (pin "5") (pinfunction "5_5") (pintype "bidirectional"))
      (node (ref "R9") (pin "1") (pinfunction "1_1") (pintype "passive"))
    )
    (net (code "24") (name "Net-(Q1-D)") (class "Default")
      (node (ref "Q1") (pin "3") (pinfunction "D_3") (pintype "bidirectional"))
      (node (ref "Q7") (pin "1") (pinfunction "G_1") (pintype "bidirectional"))
      (node (ref "R41") (pin "1") (pinfunction "1_1") (pintype "passive"))
    )
    (net (code "25") (name "Net-(Q2-D)") (class "Default")
      (node (ref "J5") (pin "2") (pinfunction "2_2") (pintype "bidirectional"))
      (node (ref "Q2") (pin "3") (pinfunction "D_3") (pintype "bidirectional"))
    )
    (net (code "26") (name "Net-(Q3-D)") (class "Default")
      (node (ref "J6") (pin "2") (pinfunction "2_2") (pintype "bidirectional"))
      (node (ref "Q3") (pin "3") (pinfunction "D_3") (pintype "bidirectional"))
    )
    (net (code "27") (name "Net-(Q4-D)") (class "Default")
      (node (ref "J7") (pin "2") (pinfunction "2_2") (pintype "bidirectional"))
      (node (ref "Q4") (pin "3") (pinfunction "D_3") (pintype "bidirectional"))
    )
    (net (code "28") (name "Net-(Q5-D)") (class "Default")
      (node (ref "J8") (pin "2") (pinfunction "2_2") (pintype "bidirectional"))
      (node (ref "Q5") (pin "3") (pinfunction "D_3") (pintype "bidirectional"))
    )
    (net (code "29") (name "Net-(Q7-D)") (class "Default")
      (node (ref "C1") (pin "1") (pinfunction "1_1") (pintype "passive"))
      (node (ref "J1") (pin "1") (pinfunction "1_1") (pintype "bidirectional"))
      (node (ref "Q7") (pin "3") (pinfunction "D_3") (pintype "bidirectional"))
    )
    (net (code "30") (name "Net-(R56-Pad1)") (class "Default")
      (node (ref "R56") (pin "1") (pinfunction "1_1") (pintype "passive"))
      (node (ref "R7") (pin "2") (pinfunction "2_2") (pintype "passive"))
      (node (ref "R8") (pin "2") (pinfunction "2_2") (pintype "passive"))
      (node (ref "SW1") (pin "1") (pinfunction "1_1") (pintype "bidirectional"))
    )
    (net (code "31") (name "Net-(U1A-+IN)") (class "Default")
      (node (ref "R11") (pin "2") (pinfunction "2_2") (pintype "passive"))
      (node (ref "R12") (pin "2") (pinfunction "2_2") (pintype "passive"))
      (node (ref "R13") (pin "1") (pinfunction "1_1") (pintype "passive"))
      (node (ref "U1") (pin "3") (pinfunction "+IN_3") (pintype "input"))
    )
    (net (code "32") (name "Net-(U1B-+IN)") (class "Default")
      (node (ref "R15") (pin "2") (pinfunction "2_2") (pintype "passive"))
      (node (ref "R16") (pin "1") (pinfunction "1_1") (pintype "passive"))
      (node (ref "R17") (pin "2") (pinfunction "2_2") (pintype "passive"))
      (node (ref "U1") (pin "5") (pinfunction "+IN_5") (pintype "input"))
    )
    (net (code "33") (name "Net-(U2A-+IN)") (class "Default")
      (node (ref "R42") (pin "2") (pinfunction "2_2") (pintype "passive"))
      (node (ref "R43") (pin "2") (pinfunction "2_2") (pintype "passive"))
      (node (ref "R44") (pin "1") (pinfunction "1_1") (pintype "passive"))
      (node (ref "U2") (pin "3") (pinfunction "+IN_3") (pintype "input"))
    )
    (net (code "34") (name "Net-(U2B-+IN)") (class "Default")
      (node (ref "R1") (pin "2") (pinfunction "2_2") (pintype "passive"))
      (node (ref "R2") (pin "1") (pinfunction "1_1") (pintype "passive"))
      (node (ref "R3") (pin "2") (pinfunction "2_2") (pintype "passive"))
      (node (ref "U2") (pin "5") (pinfunction "+IN_5") (pintype "input"))
    )
    (net (code "35") (name "Net-(U3-DA)") (class "Default")
      (node (ref "C3") (pin "1") (pinfunction "1_1") (pintype "passive"))
      (node (ref "R19") (pin "1") (pinfunction "1_1") (pintype "passive"))
      (node (ref "U3") (pin "1") (pinfunction "DA_1") (pintype "passive"))
    )
    (net (code "36") (name "Net-(U4-DA)") (class "Default")
      (node (ref "C4") (pin "1") (pinfunction "1_1") (pintype "passive"))
      (node (ref "R21") (pin "1") (pinfunction "1_1") (pintype "passive"))
      (node (ref "U4") (pin "1") (pinfunction "DA_1") (pintype "passive"))
    )
    (net (code "37") (name "Net-(U5-DA)") (class "Default")
      (node (ref "C5") (pin "1") (pinfunction "1_1") (pintype "passive"))
      (node (ref "R23") (pin "1") (pinfunction "1_1") (pintype "passive"))
      (node (ref "U5") (pin "1") (pinfunction "DA_1") (pintype "passive"))
    )
    (net (code "38") (name "Net-(U6-ADJ)") (class "Default")
      (node (ref "R27") (pin "1") (pinfunction "1_1") (pintype "passive"))
      (node (ref "R28") (pin "2") (pinfunction "2_2") (pintype "passive"))
      (node (ref "U6") (pin "1") (pinfunction "ADJ_1") (pintype "bidirectional"))
    )
    (net (code "39") (name "Net-(U7-OUT)") (class "Default")
      (node (ref "R57") (pin "1") (pinfunction "1_1") (pintype "passive"))
      (node (ref "U7") (pin "2") (pinfunction "OUT_2") (pintype "bidirectional"))
    )
    (net (code "40") (name "Net-(U8-OUT1)") (class "Default")
      (node (ref "J4") (pin "4") (pinfunction "4_4") (pintype "bidirectional"))
      (node (ref "U8") (pin "10") (pinfunction "OUT1_10") (pintype "bidirectional"))
    )
    (net (code "41") (name "Net-(U8-OUT2)") (class "Default")
      (node (ref "J4") (pin "3") (pinfunction "3_3") (pintype "bidirectional"))
      (node (ref "U8") (pin "9") (pinfunction "OUT2_9") (pintype "bidirectional"))
    )
    (net (code "42") (name "Net-(U8-OUT3)") (class "Default")
      (node (ref "J4") (pin "2") (pinfunction "2_2") (pintype "bidirectional"))
      (node (ref "U8") (pin "7") (pinfunction "OUT3_7") (pintype "bidirectional"))
    )
    (net (code "43") (name "Net-(U8-OUT4)") (class "Default")
      (node (ref "J4") (pin "1") (pinfunction "1_1") (pintype "bidirectional"))
      (node (ref "U8") (pin "6") (pinfunction "OUT4_6") (pintype "bidirectional"))
    )
    (net (code "44") (name "Net-(U10-DA)") (class "Default")
      (node (ref "C21") (pin "1") (pinfunction "1_1") (pintype "passive"))
      (node (ref "R47") (pin "1") (pinfunction "1_1") (pintype "passive"))
      (node (ref "U10") (pin "1") (pinfunction "DA_1") (pintype "passive"))
    )
    (net (code "45") (name "RST") (class "Default")
      (node (ref "P1") (pin "3") (pinfunction "3_3") (pintype "bidirectional"))
      (node (ref "R32") (pin "1") (pinfunction "1_1") (pintype "passive"))
      (node (ref "R33") (pin "2") (pinfunction "2_2") (pintype "passive"))
    )
    (net (code "46") (name "SOL_EN") (class "Default")
      (node (ref "P4") (pin "6") (pinfunction "6_6") (pintype "bidirectional"))
      (node (ref "Q1") (pin "2") (pinfunction "G_2") (pintype "bidirectional"))
      (node (ref "R34") (pin "2") (pinfunction "2_2") (pintype "passive"))
    )
    (net (code "47") (name "VCC") (class "Default")
      (node (ref "C12") (pin "P$1") (pinfunction "1_P$1") (pintype "passive"))
      (node (ref "C20") (pin "1") (pinfunction "1_1") (pintype "passive"))
      (node (ref "C6") (pin "1") (pinfunction "1_1") (pintype "passive"))
      (node (ref "C7") (pin "1") (pinfunction "1_1") (pintype "passive"))
      (node (ref "J3") (pin "1") (pinfunction "1_1") (pintype "bidirectional"))
      (node (ref "Q7") (pin "2") (pinfunction "S_2") (pintype "bidirectional"))
      (node (ref "R35") (pin "2") (pinfunction "2_2") (pintype "passive"))
      (node (ref "R41") (pin "2") (pinfunction "2_2") (pintype "passive"))
      (node (ref "U6") (pin "2") (pinfunction "IN_2") (pintype "bidirectional"))
      (node (ref "U8") (pin "3") (pinfunction "VBB_3") (pintype "bidirectional"))
    )
    (net (code "48") (name "VCOPT1") (class "Default")
      (node (ref "J2") (pin "2") (pinfunction "2_2") (pintype "bidirectional"))
      (node (ref "P2") (pin "1") (pinfunction "1_1") (pintype "bidirectional"))
    )
    (net (code "49") (name "VCOPT2") (class "Default")
      (node (ref "J2") (pin "3") (pinfunction "3_3") (pintype "bidirectional"))
      (node (ref "P2") (pin "2") (pinfunction "2_2") (pintype "bidirectional"))
    )
    (net (code "50") (name "VCOPT3") (class "Default")
      (node (ref "J2") (pin "4") (pinfunction "4_4") (pintype "bidirectional"))
      (node (ref "P2") (pin "3") (pinfunction "3_3") (pintype "bidirectional"))
    )
    (net (code "51") (name "VCOPT4") (class "Default")
      (node (ref "J2") (pin "5") (pinfunction "5_5") (pintype "bidirectional"))
      (node (ref "P2") (pin "4") (pinfunction "4_4") (pintype "bidirectional"))
    )
    (net (code "52") (name "VDD") (class "Default")
      (node (ref "C11") (pin "1") (pinfunction "1_1") (pintype "passive"))
      (node (ref "C13") (pin "1") (pinfunction "1_1") (pintype "passive"))
      (node (ref "C14") (pin "1") (pinfunction "1_1") (pintype "passive"))
      (node (ref "C15") (pin "1") (pinfunction "1_1") (pintype "passive"))
      (node (ref "C16") (pin "1") (pinfunction "1_1") (pintype "passive"))
      (node (ref "C17") (pin "1") (pinfunction "1_1") (pintype "passive"))
      (node (ref "C18") (pin "1") (pinfunction "1_1") (pintype "passive"))
      (node (ref "C19") (pin "1") (pinfunction "1_1") (pintype "passive"))
      (node (ref "C2") (pin "1") (pinfunction "1_1") (pintype "passive"))
      (node (ref "C23") (pin "1") (pinfunction "1_1") (pintype "passive"))
      (node (ref "C28") (pin "1") (pinfunction "1_1") (pintype "passive"))
      (node (ref "C29") (pin "1") (pinfunction "1_1") (pintype "passive"))
      (node (ref "J2") (pin "1") (pinfunction "1_1") (pintype "bidirectional"))
      (node (ref "R12") (pin "1") (pinfunction "1_1") (pintype "passive"))
      (node (ref "R17") (pin "1") (pinfunction "1_1") (pintype "passive"))
      (node (ref "R19") (pin "2") (pinfunction "2_2") (pintype "passive"))
      (node (ref "R20") (pin "2") (pinfunction "2_2") (pintype "passive"))
      (node (ref "R21") (pin "2") (pinfunction "2_2") (pintype "passive"))
      (node (ref "R22") (pin "2") (pinfunction "2_2") (pintype "passive"))
      (node (ref "R23") (pin "2") (pinfunction "2_2") (pintype "passive"))
      (node (ref "R24") (pin "2") (pinfunction "2_2") (pintype "passive"))
      (node (ref "R25") (pin "2") (pinfunction "2_2") (pintype "passive"))
      (node (ref "R26") (pin "2") (pinfunction "2_2") (pintype "passive"))
      (node (ref "R27") (pin "2") (pinfunction "2_2") (pintype "passive"))
      (node (ref "R3") (pin "1") (pinfunction "1_1") (pintype "passive"))
      (node (ref "R32") (pin "2") (pinfunction "2_2") (pintype "passive"))
      (node (ref "R36") (pin "2") (pinfunction "2_2") (pintype "passive"))
      (node (ref "R38") (pin "2") (pinfunction "2_2") (pintype "passive"))
      (node (ref "R39") (pin "2") (pinfunction "2_2") (pintype "passive"))
      (node (ref "R43") (pin "1") (pinfunction "1_1") (pintype "passive"))
      (node (ref "R45") (pin "2") (pinfunction "2_2") (pintype "passive"))
      (node (ref "R46") (pin "2") (pinfunction "2_2") (pintype "passive"))
      (node (ref "R47") (pin "2") (pinfunction "2_2") (pintype "passive"))
      (node (ref "R48") (pin "2") (pinfunction "2_2") (pintype "passive"))
      (node (ref "R5") (pin "2") (pinfunction "2_2") (pintype "passive"))
      (node (ref "R50") (pin "2") (pinfunction "2_2") (pintype "passive"))
      (node (ref "R52") (pin "2") (pinfunction "2_2") (pintype "passive"))
      (node (ref "R53") (pin "2") (pinfunction "2_2") (pintype "passive"))
      (node (ref "R54") (pin "2") (pinfunction "2_2") (pintype "passive"))
      (node (ref "R55") (pin "2") (pinfunction "2_2") (pintype "passive"))
      (node (ref "R56") (pin "2") (pinfunction "2_2") (pintype "passive"))
      (node (ref "R9") (pin "2") (pinfunction "2_2") (pintype "passive"))
      (node (ref "SW1") (pin "2") (pinfunction "2_2") (pintype "bidirectional"))
      (node (ref "U1") (pin "8") (pinfunction "V+_8") (pintype "power_in"))
      (node (ref "U2") (pin "8") (pinfunction "V+_8") (pintype "power_in"))
      (node (ref "U6") (pin "3") (pinfunction "OUT_3") (pintype "bidirectional"))
      (node (ref "U7") (pin "1") (pinfunction "VDD_1") (pintype "bidirectional"))
    )
    (net (code "53") (name "VMAG") (class "Default")
      (node (ref "C30") (pin "1") (pinfunction "1_1") (pintype "passive"))
      (node (ref "P2") (pin "6") (pinfunction "6_6") (pintype "bidirectional"))
      (node (ref "R57") (pin "2") (pinfunction "2_2") (pintype "passive"))
    )
    (net (code "54") (name "VOPT1") (class "Default")
      (node (ref "P3") (pin "5") (pinfunction "5_5") (pintype "bidirectional"))
      (node (ref "R11") (pin "1") (pinfunction "1_1") (pintype "passive"))
      (node (ref "R14") (pin "1") (pinfunction "1_1") (pintype "passive"))
      (node (ref "R25") (pin "1") (pinfunction "1_1") (pintype "passive"))
      (node (ref "U1") (pin "1") (pinfunction "OUT_1") (pintype "output"))
    )
    (net (code "55") (name "VOPT2") (class "Default")
      (node (ref "P3") (pin "6") (pinfunction "6_6") (pintype "bidirectional"))
      (node (ref "R15") (pin "1") (pinfunction "1_1") (pintype "passive"))
      (node (ref "R18") (pin "1") (pinfunction "1_1") (pintype "passive"))
      (node (ref "R26") (pin "1") (pinfunction "1_1") (pintype "passive"))
      (node (ref "U1") (pin "7") (pinfunction "OUT_7") (pintype "output"))
    )
    (net (code "56") (name "VOPT3") (class "Default")
      (node (ref "P3") (pin "7") (pinfunction "7_7") (pintype "bidirectional"))
      (node (ref "R42") (pin "1") (pinfunction "1_1") (pintype "passive"))
      (node (ref "R46") (pin "1") (pinfunction "1_1") (pintype "passive"))
      (node (ref "R6") (pin "1") (pinfunction "1_1") (pintype "passive"))
      (node (ref "U2") (pin "1") (pinfunction "OUT_1") (pintype "output"))
    )
    (net (code "57") (name "VOPT4") (class "Default")
      (node (ref "P3") (pin "8") (pinfunction "8_8") (pintype "bidirectional"))
      (node (ref "R1") (pin "1") (pinfunction "1_1") (pintype "passive"))
      (node (ref "R4") (pin "1") (pinfunction "1_1") (pintype "passive"))
      (node (ref "R5") (pin "1") (pinfunction "1_1") (pintype "passive"))
      (node (ref "U2") (pin "7") (pinfunction "OUT_7") (pintype "output"))
    )
    (net (code "58") (name "VRING1") (class "Default")
      (node (ref "C8") (pin "1") (pinfunction "1_1") (pintype "passive"))
      (node (ref "R14") (pin "2") (pinfunction "2_2") (pintype "passive"))
      (node (ref "R20") (pin "1") (pinfunction "1_1") (pintype "passive"))
      (node (ref "U1") (pin "2") (pinfunction "-IN_2") (pintype "input"))
      (node (ref "U3") (pin "3") (pinfunction "C_3") (pintype "passive"))
    )
    (net (code "59") (name "VRING2") (class "Default")
      (node (ref "C9") (pin "1") (pinfunction "1_1") (pintype "passive"))
      (node (ref "R18") (pin "2") (pinfunction "2_2") (pintype "passive"))
      (node (ref "R22") (pin "1") (pinfunction "1_1") (pintype "passive"))
      (node (ref "U1") (pin "6") (pinfunction "-IN_6") (pintype "input"))
      (node (ref "U4") (pin "3") (pinfunction "C_3") (pintype "passive"))
    )
    (net (code "60") (name "VRING3") (class "Default")
      (node (ref "C22") (pin "1") (pinfunction "1_1") (pintype "passive"))
      (node (ref "R48") (pin "1") (pinfunction "1_1") (pintype "passive"))
      (node (ref "R6") (pin "2") (pinfunction "2_2") (pintype "passive"))
      (node (ref "U10") (pin "3") (pinfunction "C_3") (pintype "passive"))
      (node (ref "U2") (pin "2") (pinfunction "-IN_2") (pintype "input"))
    )
    (net (code "61") (name "VRING4") (class "Default")
      (node (ref "C10") (pin "1") (pinfunction "1_1") (pintype "passive"))
      (node (ref "R24") (pin "1") (pinfunction "1_1") (pintype "passive"))
      (node (ref "R4") (pin "2") (pinfunction "2_2") (pintype "passive"))
      (node (ref "U2") (pin "6") (pinfunction "-IN_6") (pintype "input"))
      (node (ref "U5") (pin "3") (pinfunction "C_3") (pintype "passive"))
    )
  )
)
